# SCHEMATIC.net
KiCad netlist of a schematic drawn in Altium Designer
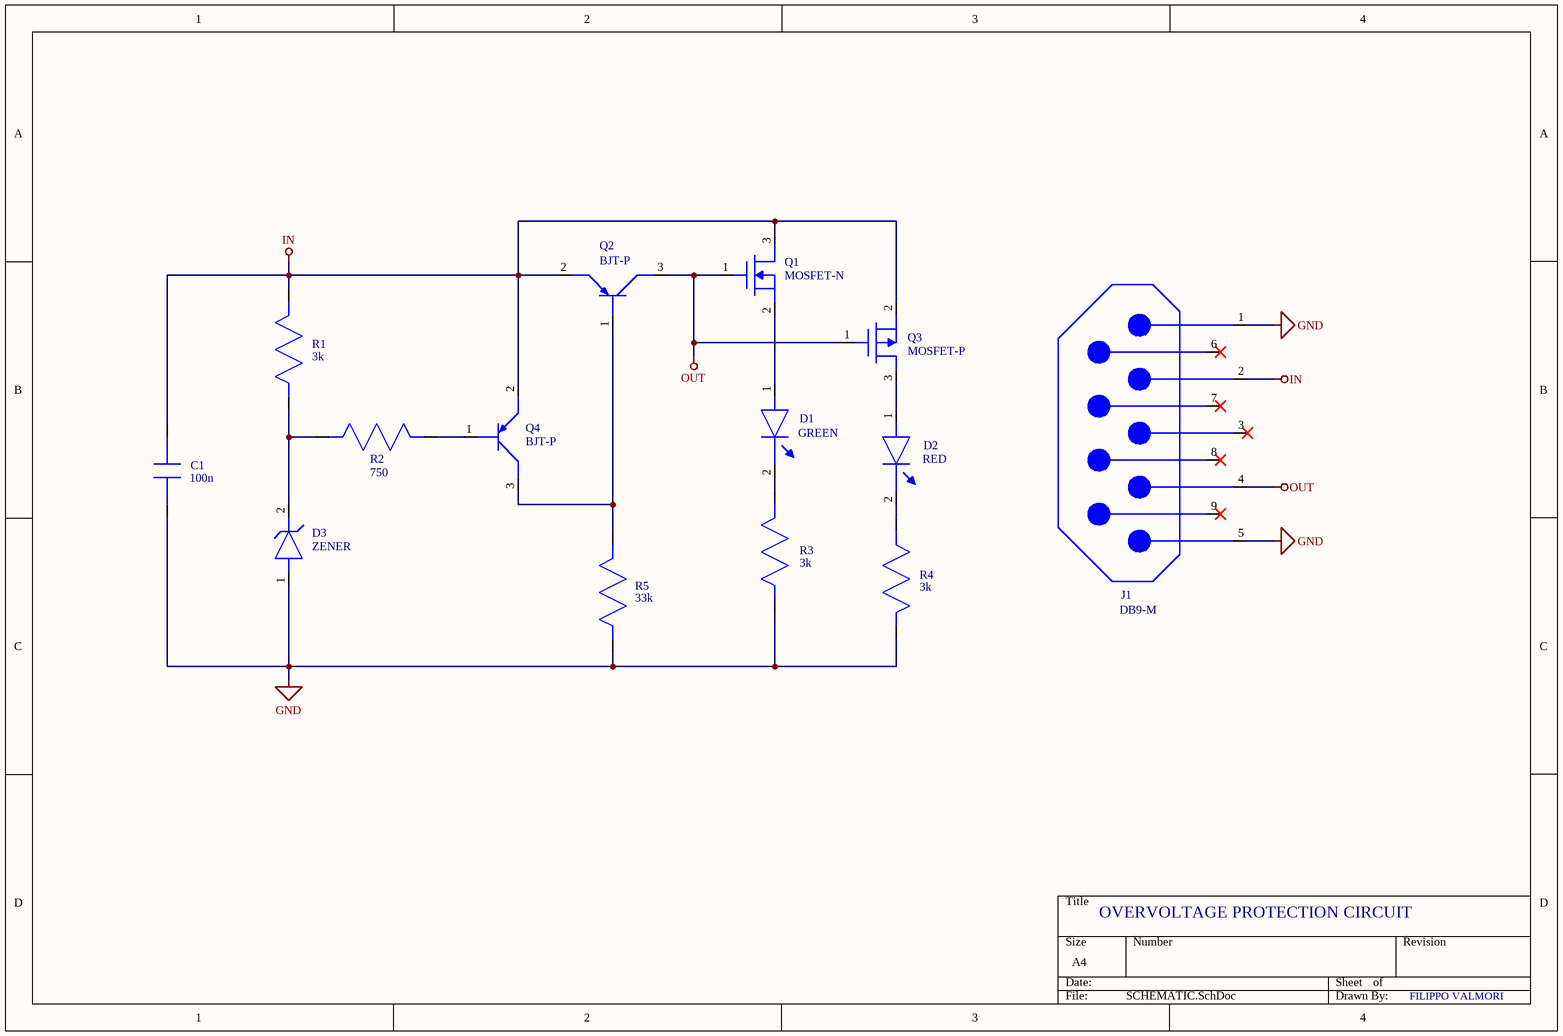
[diagram p0: SCHEMATIC.SchDoc]

(export (version "E")
  (design (tool "Eeschema 10.0.6"))
  (components
    (comp (ref "C1")
      (value "100n")
      (footprint "CAP-0603")
      (description "Multilayer Ceramic Capacitors MLCC - SMD/SMT 25volts 0.1uF X7R 20%")
      (fields
        (field (name "MANUFACTURER") "KEMET")
        (field (name "MANUFACTURER PART NUMBER") "C0603C104M3RACTU")
      )
      (libsource (lib "LIBRARY_SCHEMATIC") (part "C0603C104M3RACTU"))
    )
    (comp (ref "D1")
      (value "GREEN")
      (footprint "LED-0603")
      (description "DIALIGHT - 5988070107F - LED, Green, SMD, 0603, 20 mA, 2 V, 570 nm")
      (fields
        (field (name "MANUFACTURER") "Dialight")
        (field (name "MANUFACTURER PART NUMBER") "598-8070-107F")
      )
      (libsource (lib "LIBRARY_SCHEMATIC") (part "598-8070-107F"))
    )
    (comp (ref "D2")
      (value "RED")
      (footprint "LED-0603")
      (description "DIALIGHT   5988020107F   LED, RED ORANGE, 150MCD, 630NM")
      (fields
        (field (name "MANUFACTURER") "Dialight")
        (field (name "MANUFACTURER PART NUMBER") "598-8020-107F")
      )
      (libsource (lib "LIBRARY_SCHEMATIC") (part "598-8020-107F"))
    )
    (comp (ref "D3")
      (value "ZENER")
      (footprint "ZENER-SOD523")
      (description "DIODE ZENER 10V 350MW SOD523")
      (fields (field (name "MANUFACTURER") "Diodes") (field (name "MANUFACTURER PART NUMBER") "BZT585B10T-7"))
      (libsource (lib "LIBRARY_SCHEMATIC") (part "BZT585B10T-7"))
    )
    (comp (ref "J1")
      (value "DB9-M")
      (footprint "DB9")
      (description "D-Sub Standard Connectors DSUB SV ML SSDP ANG73-254 09P AU3")
      (fields
        (field (name "MANUFACTURER") "HARTING Technology")
        (field (name "MANUFACTURER PART NUMBER") "09661227801")
      )
      (libsource (lib "LIBRARY_SCHEMATIC") (part "09661227801"))
    )
    (comp (ref "Q1")
      (value "MOSFET-N")
      (footprint "NMOS-SOT23")
      (description "Trans MOSFET N-CH 60V 0.115A 3-Pin SOT-23 T/R")
      (fields
        (field (name "MANUFACTURER") "ON Semiconductor")
        (field (name "MANUFACTURER PART NUMBER") "2N7002LT1G")
      )
      (libsource (lib "LIBRARY_SCHEMATIC") (part "2N7002LT1G"))
    )
    (comp (ref "Q2")
      (value "BJT-P")
      (footprint "BJT-SOT23")
      (description "MMBT2907AL Series 60 V 600 mA SMT PNP General Purpose Transistor - SOT-23")
      (fields
        (field (name "MANUFACTURER") "ON Semiconductor")
        (field (name "MANUFACTURER PART NUMBER") "MMBT2907ALT1G")
      )
      (libsource (lib "LIBRARY_SCHEMATIC") (part "MMBT2907ALT1G"))
    )
    (comp (ref "Q3")
      (value "MOSFET-P")
      (footprint "PMOS-SOT23")
      (description "MOSFET P-CH 60V 185MA SOT23-3")
      (fields
        (field (name "MANUFACTURER") "Vishay")
        (field (name "MANUFACTURER PART NUMBER") "TP0610K-T1-E3")
      )
      (libsource (lib "LIBRARY_SCHEMATIC") (part "TP0610K-T1-E3"))
    )
    (comp (ref "Q4")
      (value "BJT-P")
      (footprint "BJT-SOT23")
      (description "MMBT2907AL Series 60 V 600 mA SMT PNP General Purpose Transistor - SOT-23")
      (fields
        (field (name "MANUFACTURER") "ON Semiconductor")
        (field (name "MANUFACTURER PART NUMBER") "MMBT2907ALT1G")
      )
      (libsource (lib "LIBRARY_SCHEMATIC") (part "MMBT2907ALT1G"))
    )
    (comp (ref "R1")
      (value "3k")
      (footprint "RES-0805")
      (description "RES SMD 3.01K OHM 1% 1/4W 0805")
      (fields
        (field (name "MANUFACTURER") "Stackpole Electronics")
        (field (name "MANUFACTURER PART NUMBER") "RNCP0805FTD3K01")
      )
      (libsource (lib "LIBRARY_SCHEMATIC") (part "RNCP0805FTD3K01"))
    )
    (comp (ref "R2")
      (value "750")
      (footprint "RES-0805")
      (description "RES SMD 750 OHM 1% 1/4W 0805")
      (fields
        (field (name "MANUFACTURER") "Stackpole Electronics")
        (field (name "MANUFACTURER PART NUMBER") "RNCP0805FTD750R")
      )
      (libsource (lib "LIBRARY_SCHEMATIC") (part "RNCP0805FTD750R"))
    )
    (comp (ref "R3")
      (value "3k")
      (footprint "RES-0805")
      (description "RES SMD 3.01K OHM 1% 1/4W 0805")
      (fields
        (field (name "MANUFACTURER") "Stackpole Electronics")
        (field (name "MANUFACTURER PART NUMBER") "RNCP0805FTD3K01")
      )
      (libsource (lib "LIBRARY_SCHEMATIC") (part "RNCP0805FTD3K01"))
    )
    (comp (ref "R4")
      (value "3k")
      (footprint "RES-0805")
      (description "RES SMD 3.01K OHM 1% 1/4W 0805")
      (fields
        (field (name "MANUFACTURER") "Stackpole Electronics")
        (field (name "MANUFACTURER PART NUMBER") "RNCP0805FTD3K01")
      )
      (libsource (lib "LIBRARY_SCHEMATIC") (part "RNCP0805FTD3K01"))
    )
    (comp (ref "R5")
      (value "33k")
      (footprint "RES-0805")
      (description "RES SMD 33.2K OHM 1% 1/4W 0805")
      (fields
        (field (name "MANUFACTURER") "Stackpole Electronics")
        (field (name "MANUFACTURER PART NUMBER") "RNCP0805FTD33K2")
      )
      (libsource (lib "LIBRARY_SCHEMATIC") (part "RNCP0805FTD33K2"))
    )
  )
  (nets
    (net (code "1") (name "GND") (class "Default")
      (node (ref "C1") (pin "2") (pinfunction "2_2") (pintype "passive"))
      (node (ref "D3") (pin "1") (pinfunction "1_1") (pintype "passive"))
      (node (ref "J1") (pin "1") (pinfunction "1_1") (pintype "passive"))
      (node (ref "J1") (pin "5") (pinfunction "5_5") (pintype "passive"))
      (node (ref "R3") (pin "1") (pinfunction "1_1") (pintype "passive"))
      (node (ref "R4") (pin "2") (pinfunction "2_2") (pintype "passive"))
      (node (ref "R5") (pin "1") (pinfunction "1_1") (pintype "passive"))
    )
    (net (code "2") (name "IN") (class "Default")
      (node (ref "C1") (pin "1") (pinfunction "1_1") (pintype "passive"))
      (node (ref "J1") (pin "2") (pinfunction "2_2") (pintype "passive"))
      (node (ref "Q1") (pin "3") (pinfunction "3_3") (pintype "passive"))
      (node (ref "Q2") (pin "2") (pinfunction "2_2") (pintype "passive"))
      (node (ref "Q3") (pin "2") (pinfunction "2_2") (pintype "passive"))
      (node (ref "Q4") (pin "2") (pinfunction "2_2") (pintype "passive"))
      (node (ref "R1") (pin "2") (pinfunction "2_2") (pintype "passive"))
    )
    (net (code "3") (name "Net-(D1-Pad1)") (class "Default")
      (node (ref "D1") (pin "1") (pinfunction "1_1") (pintype "passive"))
      (node (ref "Q1") (pin "2") (pinfunction "2_2") (pintype "passive"))
    )
    (net (code "4") (name "Net-(D1-Pad2)") (class "Default")
      (node (ref "D1") (pin "2") (pinfunction "2_2") (pintype "passive"))
      (node (ref "R3") (pin "2") (pinfunction "2_2") (pintype "passive"))
    )
    (net (code "5") (name "Net-(D2-Pad1)") (class "Default")
      (node (ref "D2") (pin "1") (pinfunction "1_1") (pintype "passive"))
      (node (ref "Q3") (pin "3") (pinfunction "3_3") (pintype "passive"))
    )
    (net (code "6") (name "Net-(D2-Pad2)") (class "Default")
      (node (ref "D2") (pin "2") (pinfunction "2_2") (pintype "passive"))
      (node (ref "R4") (pin "1") (pinfunction "1_1") (pintype "passive"))
    )
    (net (code "7") (name "Net-(D3-Pad2)") (class "Default")
      (node (ref "D3") (pin "2") (pinfunction "2_2") (pintype "passive"))
      (node (ref "R1") (pin "1") (pinfunction "1_1") (pintype "passive"))
      (node (ref "R2") (pin "1") (pinfunction "1_1") (pintype "passive"))
    )
    (net (code "8") (name "Net-(Q2-Pad1)") (class "Default")
      (node (ref "Q2") (pin "1") (pinfunction "1_1") (pintype "passive"))
      (node (ref "Q4") (pin "3") (pinfunction "3_3") (pintype "passive"))
      (node (ref "R5") (pin "2") (pinfunction "2_2") (pintype "passive"))
    )
    (net (code "9") (name "Net-(Q4-Pad1)") (class "Default")
      (node (ref "Q4") (pin "1") (pinfunction "1_1") (pintype "passive"))
      (node (ref "R2") (pin "2") (pinfunction "2_2") (pintype "passive"))
    )
    (net (code "10") (name "OUT") (class "Default")
      (node (ref "J1") (pin "4") (pinfunction "4_4") (pintype "passive"))
      (node (ref "Q1") (pin "1") (pinfunction "1_1") (pintype "passive"))
      (node (ref "Q2") (pin "3") (pinfunction "3_3") (pintype "passive"))
      (node (ref "Q3") (pin "1") (pinfunction "1_1") (pintype "passive"))
    )
    (net (code "11") (name "unconnected-(J1-Pad3)") (class "Default")
      (node (ref "J1") (pin "3") (pinfunction "3_3") (pintype "passive+no_connect"))
    )
    (net (code "12") (name "unconnected-(J1-Pad6)") (class "Default")
      (node (ref "J1") (pin "6") (pinfunction "6_6") (pintype "passive+no_connect"))
    )
    (net (code "13") (name "unconnected-(J1-Pad7)") (class "Default")
      (node (ref "J1") (pin "7") (pinfunction "7_7") (pintype "passive+no_connect"))
    )
    (net (code "14") (name "unconnected-(J1-Pad8)") (class "Default")
      (node (ref "J1") (pin "8") (pinfunction "8_8") (pintype "passive+no_connect"))
    )
    (net (code "15") (name "unconnected-(J1-Pad9)") (class "Default")
      (node (ref "J1") (pin "9") (pinfunction "9_9") (pintype "passive+no_connect"))
    )
  )
)
